# BOT_Input_board.net
KiCad netlist of a schematic drawn in EAGLE
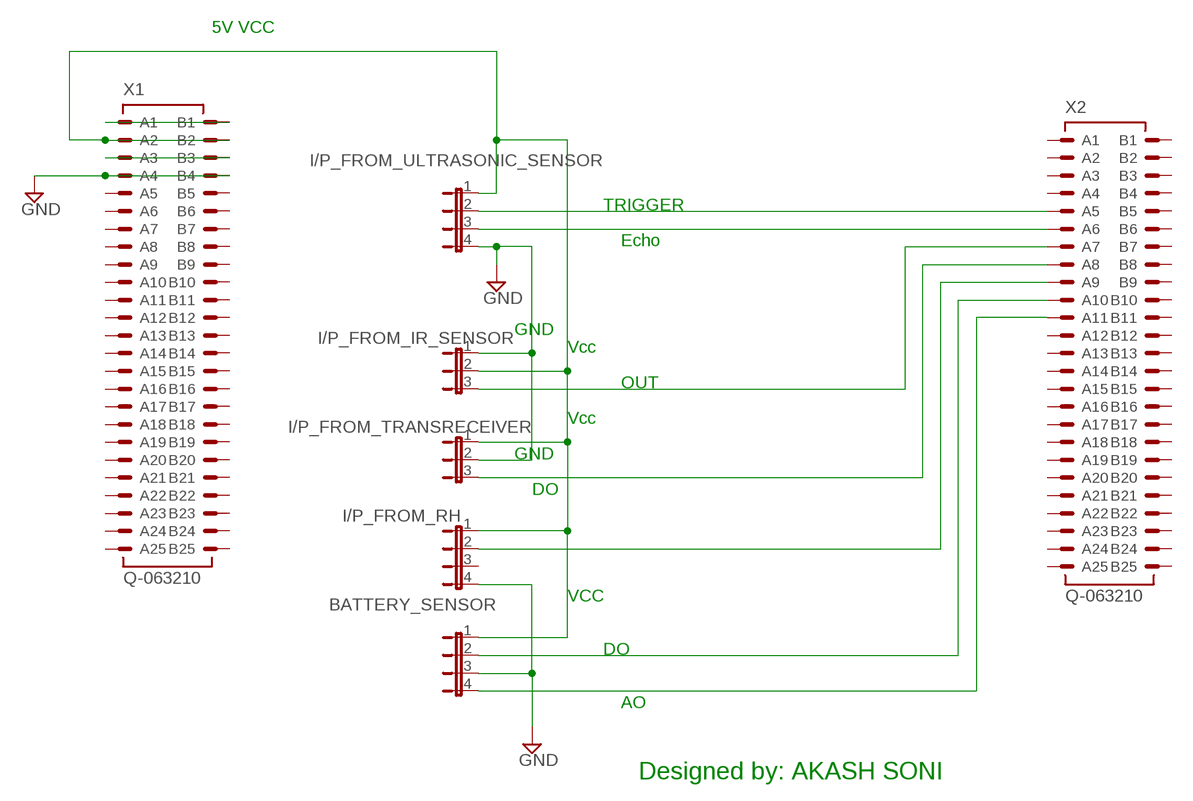
[diagram p0: schematic, sheet 1]

(export (version "E")
  (design (tool "Eeschema 10.0.6"))
  (components
    (comp (ref "BATTERY_SENSOR")
      (value "JP4E")
      (footprint "eagle-import:JP4")
      (libsource (lib "eagle-import") (part "JP4E"))
    )
    (comp (ref "I/P_FROM_IR_SENSOR")
      (value "JP2E")
      (footprint "eagle-import:JP2")
      (libsource (lib "eagle-import") (part "JP2E"))
    )
    (comp (ref "I/P_FROM_RH")
      (value "JP4E")
      (footprint "eagle-import:JP4")
      (libsource (lib "eagle-import") (part "JP4E"))
    )
    (comp (ref "I/P_FROM_TRANSRECEIVER")
      (value "JP2E")
      (footprint "eagle-import:JP2")
      (libsource (lib "eagle-import") (part "JP2E"))
    )
    (comp (ref "I/P_FROM_ULTRASONIC_SENSOR")
      (value "JP4E")
      (footprint "eagle-import:JP4")
      (libsource (lib "eagle-import") (part "JP4E"))
    )
    (comp (ref "X1")
      (value "Q-063210")
      (footprint "eagle-import:063210")
      (libsource (lib "eagle-import") (part "Q-063210"))
    )
    (comp (ref "X2")
      (value "Q-063210")
      (footprint "eagle-import:063210")
      (libsource (lib "eagle-import") (part "Q-063210"))
    )
  )
  (nets
    (net (code "1") (name "GND") (class "Default")
      (node (ref "BATTERY_SENSOR") (pin "3") (pinfunction "3_3") (pintype "passive"))
      (node (ref "I/P_FROM_IR_SENSOR") (pin "1") (pinfunction "1_1") (pintype "passive"))
      (node (ref "I/P_FROM_RH") (pin "4") (pinfunction "4_4") (pintype "passive"))
      (node (ref "I/P_FROM_TRANSRECEIVER") (pin "2") (pinfunction "2_2") (pintype "passive"))
      (node (ref "I/P_FROM_ULTRASONIC_SENSOR") (pin "4") (pinfunction "4_4") (pintype "passive"))
      (node (ref "X1") (pin "A4") (pinfunction "A4_A4") (pintype "passive"))
      (node (ref "X1") (pin "B4") (pinfunction "B4_B4") (pintype "passive"))
    )
    (net (code "2") (name "Net-(BATTERY_SENSOR-Pad1)") (class "Default")
      (node (ref "BATTERY_SENSOR") (pin "1") (pinfunction "1_1") (pintype "passive"))
      (node (ref "I/P_FROM_IR_SENSOR") (pin "2") (pinfunction "2_2") (pintype "passive"))
      (node (ref "I/P_FROM_RH") (pin "1") (pinfunction "1_1") (pintype "passive"))
      (node (ref "I/P_FROM_TRANSRECEIVER") (pin "1") (pinfunction "1_1") (pintype "passive"))
      (node (ref "I/P_FROM_ULTRASONIC_SENSOR") (pin "1") (pinfunction "1_1") (pintype "passive"))
      (node (ref "X1") (pin "A2") (pinfunction "A2_A2") (pintype "passive"))
      (node (ref "X1") (pin "B2") (pinfunction "B2_B2") (pintype "passive"))
    )
    (net (code "3") (name "Net-(BATTERY_SENSOR-Pad2)") (class "Default")
      (node (ref "BATTERY_SENSOR") (pin "2") (pinfunction "2_2") (pintype "passive"))
      (node (ref "X2") (pin "A10") (pinfunction "A10_A10") (pintype "passive"))
    )
    (net (code "4") (name "Net-(BATTERY_SENSOR-Pad4)") (class "Default")
      (node (ref "BATTERY_SENSOR") (pin "4") (pinfunction "4_4") (pintype "passive"))
      (node (ref "X2") (pin "A11") (pinfunction "A11_A11") (pintype "passive"))
    )
    (net (code "5") (name "Net-(I/P_FROM_IR_SENSOR-Pad3)") (class "Default")
      (node (ref "I/P_FROM_IR_SENSOR") (pin "3") (pinfunction "3_3") (pintype "passive"))
      (node (ref "X2") (pin "A7") (pinfunction "A7_A7") (pintype "passive"))
    )
    (net (code "6") (name "Net-(I/P_FROM_RH-Pad2)") (class "Default")
      (node (ref "I/P_FROM_RH") (pin "2") (pinfunction "2_2") (pintype "passive"))
      (node (ref "X2") (pin "A9") (pinfunction "A9_A9") (pintype "passive"))
    )
    (net (code "7") (name "Net-(I/P_FROM_TRANSRECEIVER-Pad3)") (class "Default")
      (node (ref "I/P_FROM_TRANSRECEIVER") (pin "3") (pinfunction "3_3") (pintype "passive"))
      (node (ref "X2") (pin "A8") (pinfunction "A8_A8") (pintype "passive"))
    )
    (net (code "8") (name "Net-(I/P_FROM_ULTRASONIC_SENSOR-Pad2)") (class "Default")
      (node (ref "I/P_FROM_ULTRASONIC_SENSOR") (pin "2") (pinfunction "2_2") (pintype "passive"))
      (node (ref "X2") (pin "A5") (pinfunction "A5_A5") (pintype "passive"))
    )
    (net (code "9") (name "Net-(I/P_FROM_ULTRASONIC_SENSOR-Pad3)") (class "Default")
      (node (ref "I/P_FROM_ULTRASONIC_SENSOR") (pin "3") (pinfunction "3_3") (pintype "passive"))
      (node (ref "X2") (pin "A6") (pinfunction "A6_A6") (pintype "passive"))
    )
    (net (code "10") (name "Net-(X1-PadA1)") (class "Default")
      (node (ref "X1") (pin "A1") (pinfunction "A1_A1") (pintype "passive"))
      (node (ref "X1") (pin "B1") (pinfunction "B1_B1") (pintype "passive"))
    )
    (net (code "11") (name "Net-(X1-PadA3)") (class "Default")
      (node (ref "X1") (pin "A3") (pinfunction "A3_A3") (pintype "passive"))
      (node (ref "X1") (pin "B3") (pinfunction "B3_B3") (pintype "passive"))
    )
    (net (code "12") (name "unconnected-(I/P_FROM_RH-Pad3)") (class "Default")
      (node (ref "I/P_FROM_RH") (pin "3") (pinfunction "3_3") (pintype "passive"))
    )
    (net (code "13") (name "unconnected-(X1-PadA5)") (class "Default")
      (node (ref "X1") (pin "A5") (pinfunction "A5_A5") (pintype "passive"))
    )
    (net (code "14") (name "unconnected-(X1-PadA6)") (class "Default")
      (node (ref "X1") (pin "A6") (pinfunction "A6_A6") (pintype "passive"))
    )
    (net (code "15") (name "unconnected-(X1-PadA7)") (class "Default")
      (node (ref "X1") (pin "A7") (pinfunction "A7_A7") (pintype "passive"))
    )
    (net (code "16") (name "unconnected-(X1-PadA8)") (class "Default")
      (node (ref "X1") (pin "A8") (pinfunction "A8_A8") (pintype "passive"))
    )
    (net (code "17") (name "unconnected-(X1-PadA9)") (class "Default")
      (node (ref "X1") (pin "A9") (pinfunction "A9_A9") (pintype "passive"))
    )
    (net (code "18") (name "unconnected-(X1-PadA10)") (class "Default")
      (node (ref "X1") (pin "A10") (pinfunction "A10_A10") (pintype "passive"))
    )
    (net (code "19") (name "unconnected-(X1-PadA11)") (class "Default")
      (node (ref "X1") (pin "A11") (pinfunction "A11_A11") (pintype "passive"))
    )
    (net (code "20") (name "unconnected-(X1-PadA12)") (class "Default")
      (node (ref "X1") (pin "A12") (pinfunction "A12_A12") (pintype "passive"))
    )
    (net (code "21") (name "unconnected-(X1-PadA13)") (class "Default")
      (node (ref "X1") (pin "A13") (pinfunction "A13_A13") (pintype "passive"))
    )
    (net (code "22") (name "unconnected-(X1-PadA14)") (class "Default")
      (node (ref "X1") (pin "A14") (pinfunction "A14_A14") (pintype "passive"))
    )
    (net (code "23") (name "unconnected-(X1-PadA15)") (class "Default")
      (node (ref "X1") (pin "A15") (pinfunction "A15_A15") (pintype "passive"))
    )
    (net (code "24") (name "unconnected-(X1-PadA16)") (class "Default")
      (node (ref "X1") (pin "A16") (pinfunction "A16_A16") (pintype "passive"))
    )
    (net (code "25") (name "unconnected-(X1-PadA17)") (class "Default")
      (node (ref "X1") (pin "A17") (pinfunction "A17_A17") (pintype "passive"))
    )
    (net (code "26") (name "unconnected-(X1-PadA18)") (class "Default")
      (node (ref "X1") (pin "A18") (pinfunction "A18_A18") (pintype "passive"))
    )
    (net (code "27") (name "unconnected-(X1-PadA19)") (class "Default")
      (node (ref "X1") (pin "A19") (pinfunction "A19_A19") (pintype "passive"))
    )
    (net (code "28") (name "unconnected-(X1-PadA20)") (class "Default")
      (node (ref "X1") (pin "A20") (pinfunction "A20_A20") (pintype "passive"))
    )
    (net (code "29") (name "unconnected-(X1-PadA21)") (class "Default")
      (node (ref "X1") (pin "A21") (pinfunction "A21_A21") (pintype "passive"))
    )
    (net (code "30") (name "unconnected-(X1-PadA22)") (class "Default")
      (node (ref "X1") (pin "A22") (pinfunction "A22_A22") (pintype "passive"))
    )
    (net (code "31") (name "unconnected-(X1-PadA23)") (class "Default")
      (node (ref "X1") (pin "A23") (pinfunction "A23_A23") (pintype "passive"))
    )
    (net (code "32") (name "unconnected-(X1-PadA24)") (class "Default")
      (node (ref "X1") (pin "A24") (pinfunction "A24_A24") (pintype "passive"))
    )
    (net (code "33") (name "unconnected-(X1-PadA25)") (class "Default")
      (node (ref "X1") (pin "A25") (pinfunction "A25_A25") (pintype "passive"))
    )
    (net (code "34") (name "unconnected-(X1-PadB5)") (class "Default")
      (node (ref "X1") (pin "B5") (pinfunction "B5_B5") (pintype "passive"))
    )
    (net (code "35") (name "unconnected-(X1-PadB6)") (class "Default")
      (node (ref "X1") (pin "B6") (pinfunction "B6_B6") (pintype "passive"))
    )
    (net (code "36") (name "unconnected-(X1-PadB7)") (class "Default")
      (node (ref "X1") (pin "B7") (pinfunction "B7_B7") (pintype "passive"))
    )
    (net (code "37") (name "unconnected-(X1-PadB8)") (class "Default")
      (node (ref "X1") (pin "B8") (pinfunction "B8_B8") (pintype "passive"))
    )
    (net (code "38") (name "unconnected-(X1-PadB9)") (class "Default")
      (node (ref "X1") (pin "B9") (pinfunction "B9_B9") (pintype "passive"))
    )
    (net (code "39") (name "unconnected-(X1-PadB10)") (class "Default")
      (node (ref "X1") (pin "B10") (pinfunction "B10_B10") (pintype "passive"))
    )
    (net (code "40") (name "unconnected-(X1-PadB11)") (class "Default")
      (node (ref "X1") (pin "B11") (pinfunction "B11_B11") (pintype "passive"))
    )
    (net (code "41") (name "unconnected-(X1-PadB12)") (class "Default")
      (node (ref "X1") (pin "B12") (pinfunction "B12_B12") (pintype "passive"))
    )
    (net (code "42") (name "unconnected-(X1-PadB13)") (class "Default")
      (node (ref "X1") (pin "B13") (pinfunction "B13_B13") (pintype "passive"))
    )
    (net (code "43") (name "unconnected-(X1-PadB14)") (class "Default")
      (node (ref "X1") (pin "B14") (pinfunction "B14_B14") (pintype "passive"))
    )
    (net (code "44") (name "unconnected-(X1-PadB15)") (class "Default")
      (node (ref "X1") (pin "B15") (pinfunction "B15_B15") (pintype "passive"))
    )
    (net (code "45") (name "unconnected-(X1-PadB16)") (class "Default")
      (node (ref "X1") (pin "B16") (pinfunction "B16_B16") (pintype "passive"))
    )
    (net (code "46") (name "unconnected-(X1-PadB17)") (class "Default")
      (node (ref "X1") (pin "B17") (pinfunction "B17_B17") (pintype "passive"))
    )
    (net (code "47") (name "unconnected-(X1-PadB18)") (class "Default")
      (node (ref "X1") (pin "B18") (pinfunction "B18_B18") (pintype "passive"))
    )
    (net (code "48") (name "unconnected-(X1-PadB19)") (class "Default")
      (node (ref "X1") (pin "B19") (pinfunction "B19_B19") (pintype "passive"))
    )
    (net (code "49") (name "unconnected-(X1-PadB20)") (class "Default")
      (node (ref "X1") (pin "B20") (pinfunction "B20_B20") (pintype "passive"))
    )
    (net (code "50") (name "unconnected-(X1-PadB21)") (class "Default")
      (node (ref "X1") (pin "B21") (pinfunction "B21_B21") (pintype "passive"))
    )
    (net (code "51") (name "unconnected-(X1-PadB22)") (class "Default")
      (node (ref "X1") (pin "B22") (pinfunction "B22_B22") (pintype "passive"))
    )
    (net (code "52") (name "unconnected-(X1-PadB23)") (class "Default")
      (node (ref "X1") (pin "B23") (pinfunction "B23_B23") (pintype "passive"))
    )
    (net (code "53") (name "unconnected-(X1-PadB24)") (class "Default")
      (node (ref "X1") (pin "B24") (pinfunction "B24_B24") (pintype "passive"))
    )
    (net (code "54") (name "unconnected-(X1-PadB25)") (class "Default")
      (node (ref "X1") (pin "B25") (pinfunction "B25_B25") (pintype "passive"))
    )
    (net (code "55") (name "unconnected-(X2-PadA1)") (class "Default")
      (node (ref "X2") (pin "A1") (pinfunction "A1_A1") (pintype "passive"))
    )
    (net (code "56") (name "unconnected-(X2-PadA2)") (class "Default")
      (node (ref "X2") (pin "A2") (pinfunction "A2_A2") (pintype "passive"))
    )
    (net (code "57") (name "unconnected-(X2-PadA3)") (class "Default")
      (node (ref "X2") (pin "A3") (pinfunction "A3_A3") (pintype "passive"))
    )
    (net (code "58") (name "unconnected-(X2-PadA4)") (class "Default")
      (node (ref "X2") (pin "A4") (pinfunction "A4_A4") (pintype "passive"))
    )
    (net (code "59") (name "unconnected-(X2-PadA12)") (class "Default")
      (node (ref "X2") (pin "A12") (pinfunction "A12_A12") (pintype "passive"))
    )
    (net (code "60") (name "unconnected-(X2-PadA13)") (class "Default")
      (node (ref "X2") (pin "A13") (pinfunction "A13_A13") (pintype "passive"))
    )
    (net (code "61") (name "unconnected-(X2-PadA14)") (class "Default")
      (node (ref "X2") (pin "A14") (pinfunction "A14_A14") (pintype "passive"))
    )
    (net (code "62") (name "unconnected-(X2-PadA15)") (class "Default")
      (node (ref "X2") (pin "A15") (pinfunction "A15_A15") (pintype "passive"))
    )
    (net (code "63") (name "unconnected-(X2-PadA16)") (class "Default")
      (node (ref "X2") (pin "A16") (pinfunction "A16_A16") (pintype "passive"))
    )
    (net (code "64") (name "unconnected-(X2-PadA17)") (class "Default")
      (node (ref "X2") (pin "A17") (pinfunction "A17_A17") (pintype "passive"))
    )
    (net (code "65") (name "unconnected-(X2-PadA18)") (class "Default")
      (node (ref "X2") (pin "A18") (pinfunction "A18_A18") (pintype "passive"))
    )
    (net (code "66") (name "unconnected-(X2-PadA19)") (class "Default")
      (node (ref "X2") (pin "A19") (pinfunction "A19_A19") (pintype "passive"))
    )
    (net (code "67") (name "unconnected-(X2-PadA20)") (class "Default")
      (node (ref "X2") (pin "A20") (pinfunction "A20_A20") (pintype "passive"))
    )
    (net (code "68") (name "unconnected-(X2-PadA21)") (class "Default")
      (node (ref "X2") (pin "A21") (pinfunction "A21_A21") (pintype "passive"))
    )
    (net (code "69") (name "unconnected-(X2-PadA22)") (class "Default")
      (node (ref "X2") (pin "A22") (pinfunction "A22_A22") (pintype "passive"))
    )
    (net (code "70") (name "unconnected-(X2-PadA23)") (class "Default")
      (node (ref "X2") (pin "A23") (pinfunction "A23_A23") (pintype "passive"))
    )
    (net (code "71") (name "unconnected-(X2-PadA24)") (class "Default")
      (node (ref "X2") (pin "A24") (pinfunction "A24_A24") (pintype "passive"))
    )
    (net (code "72") (name "unconnected-(X2-PadA25)") (class "Default")
      (node (ref "X2") (pin "A25") (pinfunction "A25_A25") (pintype "passive"))
    )
    (net (code "73") (name "unconnected-(X2-PadB1)") (class "Default")
      (node (ref "X2") (pin "B1") (pinfunction "B1_B1") (pintype "passive"))
    )
    (net (code "74") (name "unconnected-(X2-PadB2)") (class "Default")
      (node (ref "X2") (pin "B2") (pinfunction "B2_B2") (pintype "passive"))
    )
    (net (code "75") (name "unconnected-(X2-PadB3)") (class "Default")
      (node (ref "X2") (pin "B3") (pinfunction "B3_B3") (pintype "passive"))
    )
    (net (code "76") (name "unconnected-(X2-PadB4)") (class "Default")
      (node (ref "X2") (pin "B4") (pinfunction "B4_B4") (pintype "passive"))
    )
    (net (code "77") (name "unconnected-(X2-PadB5)") (class "Default")
      (node (ref "X2") (pin "B5") (pinfunction "B5_B5") (pintype "passive"))
    )
    (net (code "78") (name "unconnected-(X2-PadB6)") (class "Default")
      (node (ref "X2") (pin "B6") (pinfunction "B6_B6") (pintype "passive"))
    )
    (net (code "79") (name "unconnected-(X2-PadB7)") (class "Default")
      (node (ref "X2") (pin "B7") (pinfunction "B7_B7") (pintype "passive"))
    )
    (net (code "80") (name "unconnected-(X2-PadB8)") (class "Default")
      (node (ref "X2") (pin "B8") (pinfunction "B8_B8") (pintype "passive"))
    )
    (net (code "81") (name "unconnected-(X2-PadB9)") (class "Default")
      (node (ref "X2") (pin "B9") (pinfunction "B9_B9") (pintype "passive"))
    )
    (net (code "82") (name "unconnected-(X2-PadB10)") (class "Default")
      (node (ref "X2") (pin "B10") (pinfunction "B10_B10") (pintype "passive"))
    )
    (net (code "83") (name "unconnected-(X2-PadB11)") (class "Default")
      (node (ref "X2") (pin "B11") (pinfunction "B11_B11") (pintype "passive"))
    )
    (net (code "84") (name "unconnected-(X2-PadB12)") (class "Default")
      (node (ref "X2") (pin "B12") (pinfunction "B12_B12") (pintype "passive"))
    )
    (net (code "85") (name "unconnected-(X2-PadB13)") (class "Default")
      (node (ref "X2") (pin "B13") (pinfunction "B13_B13") (pintype "passive"))
    )
    (net (code "86") (name "unconnected-(X2-PadB14)") (class "Default")
      (node (ref "X2") (pin "B14") (pinfunction "B14_B14") (pintype "passive"))
    )
    (net (code "87") (name "unconnected-(X2-PadB15)") (class "Default")
      (node (ref "X2") (pin "B15") (pinfunction "B15_B15") (pintype "passive"))
    )
    (net (code "88") (name "unconnected-(X2-PadB16)") (class "Default")
      (node (ref "X2") (pin "B16") (pinfunction "B16_B16") (pintype "passive"))
    )
    (net (code "89") (name "unconnected-(X2-PadB17)") (class "Default")
      (node (ref "X2") (pin "B17") (pinfunction "B17_B17") (pintype "passive"))
    )
    (net (code "90") (name "unconnected-(X2-PadB18)") (class "Default")
      (node (ref "X2") (pin "B18") (pinfunction "B18_B18") (pintype "passive"))
    )
    (net (code "91") (name "unconnected-(X2-PadB19)") (class "Default")
      (node (ref "X2") (pin "B19") (pinfunction "B19_B19") (pintype "passive"))
    )
    (net (code "92") (name "unconnected-(X2-PadB20)") (class "Default")
      (node (ref "X2") (pin "B20") (pinfunction "B20_B20") (pintype "passive"))
    )
    (net (code "93") (name "unconnected-(X2-PadB21)") (class "Default")
      (node (ref "X2") (pin "B21") (pinfunction "B21_B21") (pintype "passive"))
    )
    (net (code "94") (name "unconnected-(X2-PadB22)") (class "Default")
      (node (ref "X2") (pin "B22") (pinfunction "B22_B22") (pintype "passive"))
    )
    (net (code "95") (name "unconnected-(X2-PadB23)") (class "Default")
      (node (ref "X2") (pin "B23") (pinfunction "B23_B23") (pintype "passive"))
    )
    (net (code "96") (name "unconnected-(X2-PadB24)") (class "Default")
      (node (ref "X2") (pin "B24") (pinfunction "B24_B24") (pintype "passive"))
    )
    (net (code "97") (name "unconnected-(X2-PadB25)") (class "Default")
      (node (ref "X2") (pin "B25") (pinfunction "B25_B25") (pintype "passive"))
    )
  )
)
